# filament_width_sensor_v3_12_opt.net
KiCad netlist of a schematic drawn in EAGLE
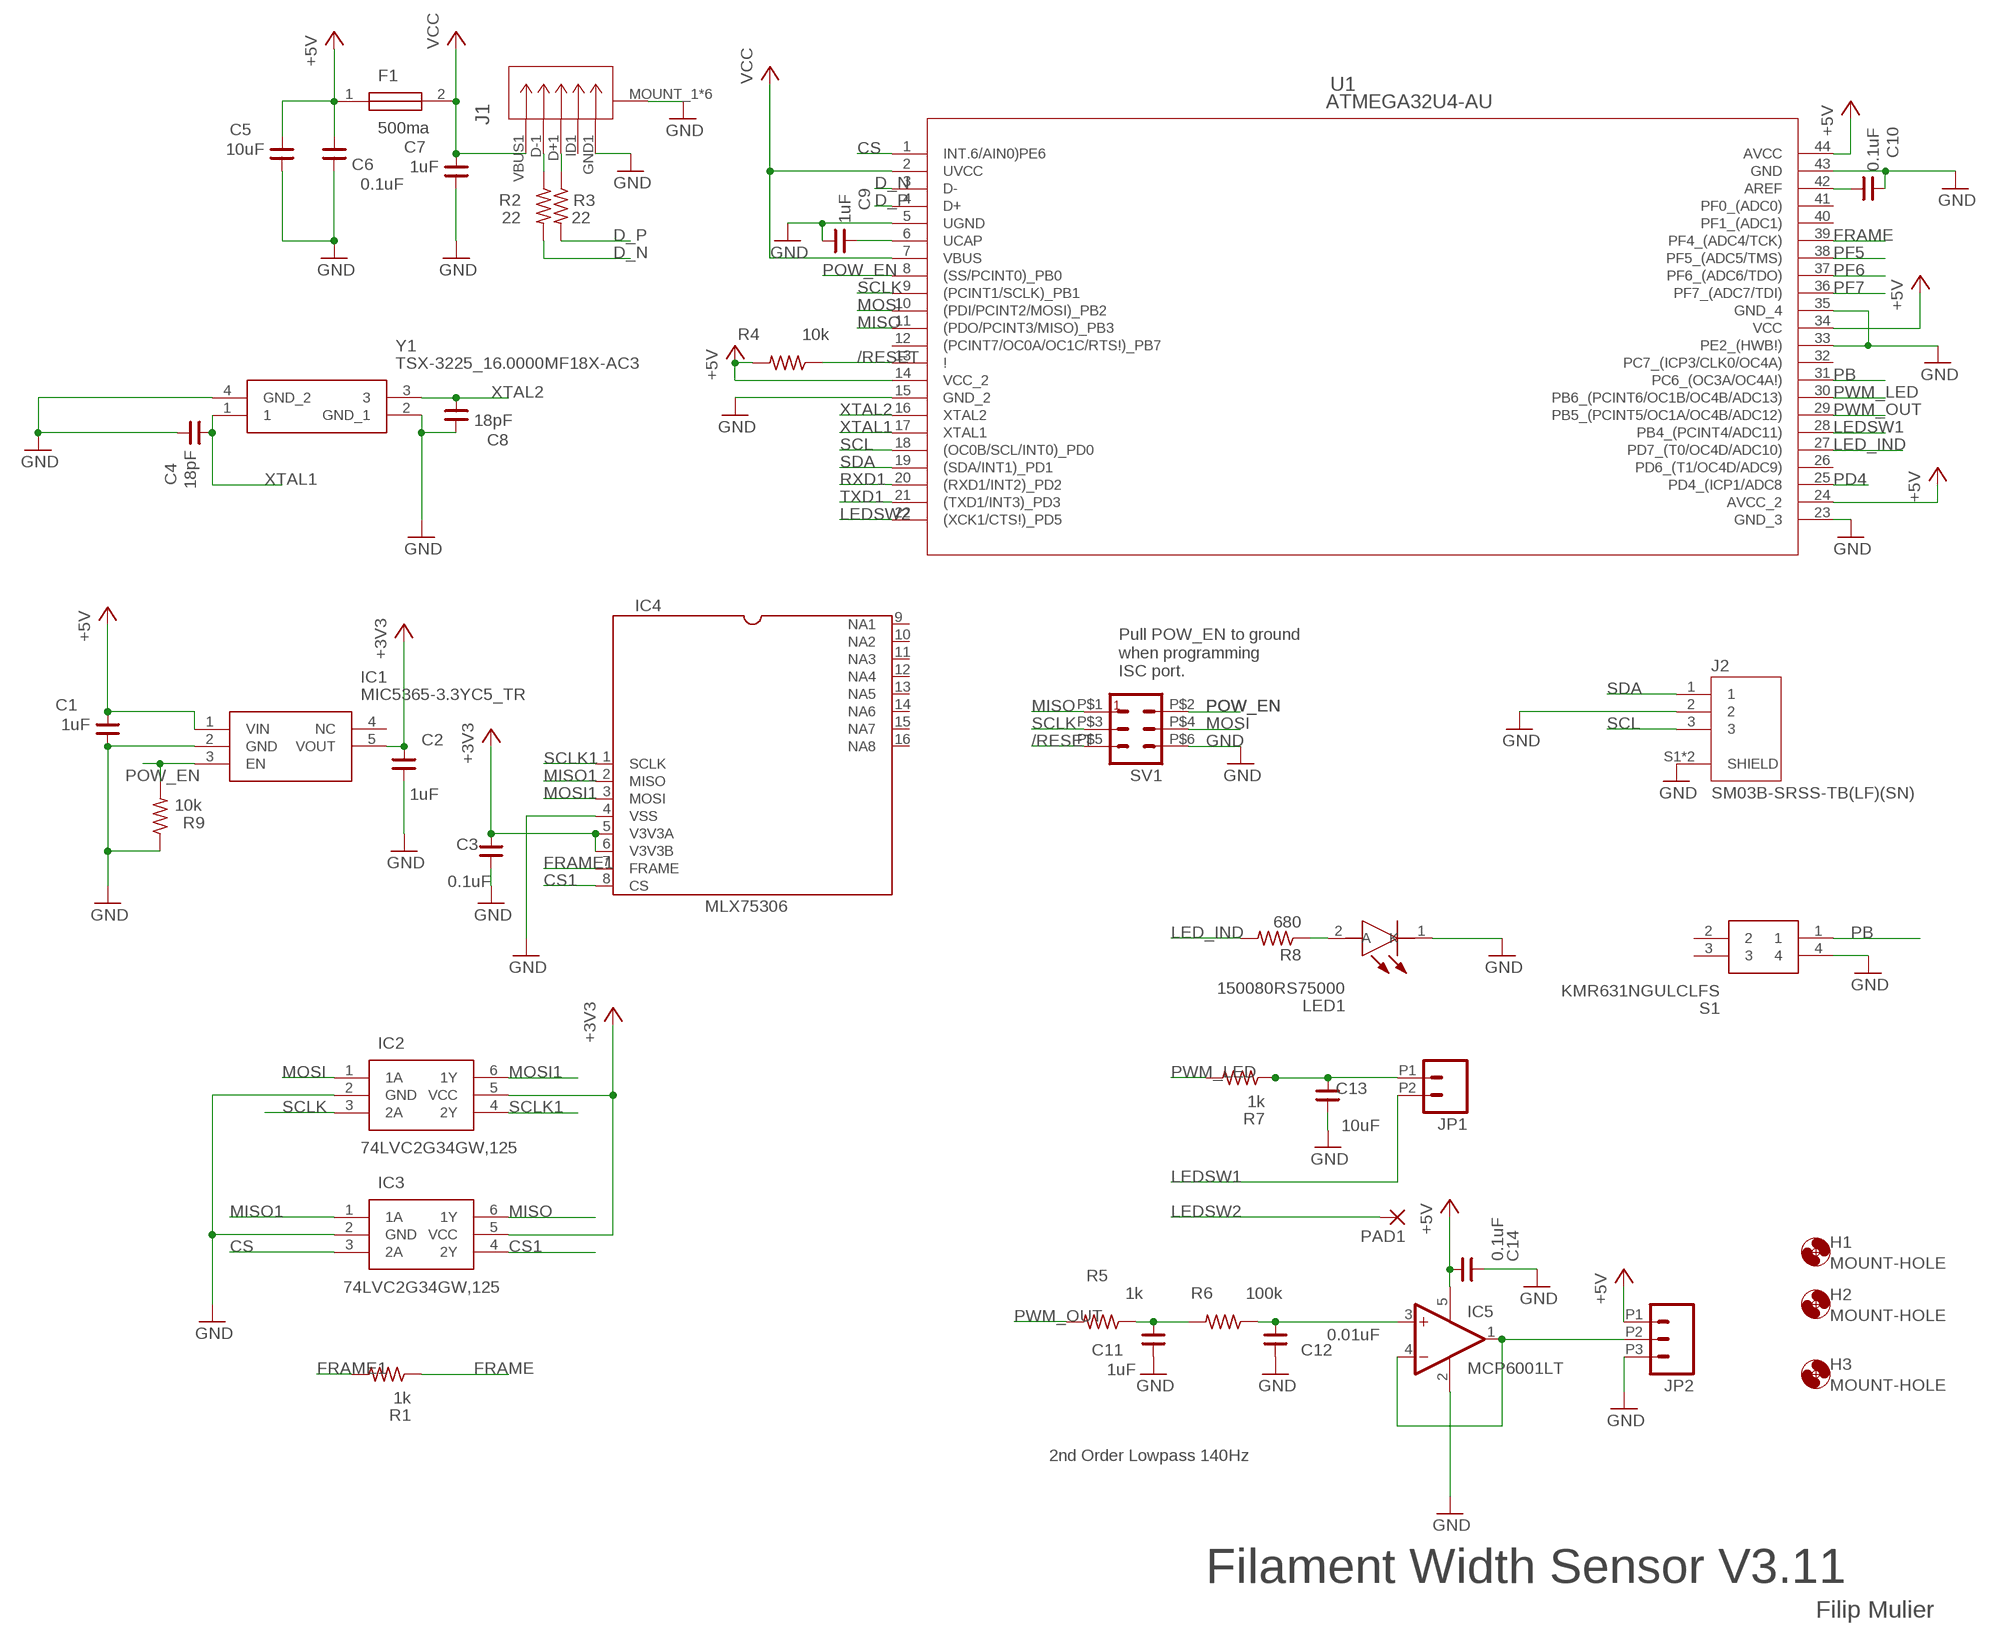
[diagram p0: schematic, sheet 1]

(export (version "E")
  (design (tool "Eeschema 10.0.6"))
  (components
    (comp (ref "C1")
      (value "1uF")
      (footprint "eagle-import:0603")
      (libsource (lib "eagle-import") (part "CNP-0603"))
    )
    (comp (ref "C2")
      (value "1uF")
      (footprint "eagle-import:0603")
      (libsource (lib "eagle-import") (part "CNP-0603"))
    )
    (comp (ref "C3")
      (value "0.1uF")
      (footprint "eagle-import:0603")
      (libsource (lib "eagle-import") (part "CNP-0603"))
    )
    (comp (ref "C4")
      (value "18pF")
      (footprint "eagle-import:0603")
      (libsource (lib "eagle-import") (part "CNP-0603"))
    )
    (comp (ref "C5")
      (value "10uF")
      (footprint "eagle-import:0805")
      (libsource (lib "eagle-import") (part "CNP-0805"))
    )
    (comp (ref "C6")
      (value "0.1uF")
      (footprint "eagle-import:0603")
      (libsource (lib "eagle-import") (part "CNP-0603"))
    )
    (comp (ref "C7")
      (value "1uF")
      (footprint "eagle-import:0603")
      (libsource (lib "eagle-import") (part "CNP-0603"))
    )
    (comp (ref "C8")
      (value "18pF")
      (footprint "eagle-import:0603")
      (libsource (lib "eagle-import") (part "CNP-0603"))
    )
    (comp (ref "C9")
      (value "1uF")
      (footprint "eagle-import:0603")
      (libsource (lib "eagle-import") (part "CNP-0603"))
    )
    (comp (ref "C10")
      (value "0.1uF")
      (footprint "eagle-import:0603")
      (libsource (lib "eagle-import") (part "CNP-0603"))
    )
    (comp (ref "C11")
      (value "1uF")
      (footprint "eagle-import:0603")
      (libsource (lib "eagle-import") (part "CNP-0603"))
    )
    (comp (ref "C12")
      (value "0.01uF")
      (footprint "eagle-import:0603")
      (libsource (lib "eagle-import") (part "CNP-0603"))
    )
    (comp (ref "C13")
      (value "10uF")
      (footprint "eagle-import:0805")
      (libsource (lib "eagle-import") (part "CNP-0805"))
    )
    (comp (ref "C14")
      (value "0.1uF")
      (footprint "eagle-import:0603")
      (libsource (lib "eagle-import") (part "CNP-0603"))
    )
    (comp (ref "F1")
      (value "500ma")
      (footprint "eagle-import:FUSC3216X75N")
      (fields (field (name "MANUFACTURER_PART_NUMBER") "0ZCJ0025FF2E"))
      (libsource (lib "eagle-import") (part "0ZCJ0025FF2E"))
    )
    (comp (ref "H1")
      (value "MOUNT-HOLE")
      (footprint "eagle-import:SCREWHOLE2-56")
      (libsource (lib "eagle-import") (part "MOUNT-HOLE"))
    )
    (comp (ref "H2")
      (value "MOUNT-HOLE")
      (footprint "eagle-import:SCREWHOLE2-56")
      (libsource (lib "eagle-import") (part "MOUNT-HOLE"))
    )
    (comp (ref "H3")
      (value "MOUNT-HOLE")
      (footprint "eagle-import:SCREWHOLE2-56")
      (libsource (lib "eagle-import") (part "MOUNT-HOLE"))
    )
    (comp (ref "IC1")
      (value "MIC5365-3.3YC5_TR")
      (footprint "eagle-import:SOT65P210X110-5N")
      (fields (field (name "MANUFACTURER_PART_NUMBER") "MIC5365-3.0YC5 TR"))
      (libsource (lib "eagle-import") (part "MIC5365-3.0YC5_TR"))
    )
    (comp (ref "IC2")
      (value "74LVC2G34GW,125")
      (footprint "eagle-import:SOP65P210X110-6N")
      (fields (field (name "MOUSER_PART_NUMBER") "771-LVC2G34GW125"))
      (libsource (lib "eagle-import") (part "74LVC2G34GW,125"))
    )
    (comp (ref "IC3")
      (value "74LVC2G34GW,125")
      (footprint "eagle-import:SOP65P210X110-6N")
      (fields (field (name "MOUSER_PART_NUMBER") "771-LVC2G34GW125"))
      (libsource (lib "eagle-import") (part "74LVC2G34GW,125"))
    )
    (comp (ref "IC4")
      (value "MLX75306")
      (footprint "eagle-import:SO16NBC")
      (libsource (lib "eagle-import") (part "MLX75306"))
    )
    (comp (ref "IC5")
      (value "MCP6001LT")
      (footprint "eagle-import:MCP6001_SC70-5")
      (libsource (lib "eagle-import") (part "MCP6001LT"))
    )
    (comp (ref "J1")
      (value "USB")
      (footprint "eagle-import:CONN5_ZX62D-B-5PA8_HIR")
      (fields (field (name "MANUFACTURER_PART_NUMBER") "ZX62D-B-5PA8(30)"))
      (libsource (lib "eagle-import") (part "ZX62D-B-5PA8(30)"))
    )
    (comp (ref "J2")
      (value "SM03B-SRSS-TB(LF)(SN)")
      (footprint "eagle-import:JST_SM03B-SRSS-TB(LF)(SN)")
      (fields (field (name "DIGI-KEY_PART_NUMBER") "455-1803-1-ND") (field (name "MF") "JST Sales"))
      (libsource (lib "eagle-import") (part "SM03B-SRSS-TB(LF)(SN)"))
    )
    (comp (ref "JP1")
      (value "M022.54MM_SCREWTERM")
      (footprint "eagle-import:1X02_2.54_SCREWTERM")
      (libsource (lib "eagle-import") (part "M022.54MM_SCREWTERM"))
    )
    (comp (ref "JP2")
      (value "M03SCREW2.54")
      (footprint "eagle-import:1X03_2.54_SCREWTERM")
      (libsource (lib "eagle-import") (part "M03SCREW2.54"))
    )
    (comp (ref "LED1")
      (value "150080RS75000")
      (footprint "eagle-import:LEDC2012X80N")
      (fields (field (name "MOUSER_PART_NUMBER") "710-150080RS75000"))
      (libsource (lib "eagle-import") (part "150080RS75000"))
    )
    (comp (ref "PAD1")
      (value "WIREPAD1,6/0,8")
      (footprint "eagle-import:1,6_0,8")
      (libsource (lib "eagle-import") (part "WIREPAD1,6/0,8"))
    )
    (comp (ref "R1")
      (value "1k")
      (footprint "eagle-import:R0603")
      (libsource (lib "eagle-import") (part "R-US_R0603"))
    )
    (comp (ref "R2")
      (value "22")
      (footprint "eagle-import:R0603")
      (libsource (lib "eagle-import") (part "R-US_R0603"))
    )
    (comp (ref "R3")
      (value "22")
      (footprint "eagle-import:R0603")
      (libsource (lib "eagle-import") (part "R-US_R0603"))
    )
    (comp (ref "R4")
      (value "10k")
      (footprint "eagle-import:R0603")
      (libsource (lib "eagle-import") (part "R-US_R0603"))
    )
    (comp (ref "R5")
      (value "1k")
      (footprint "eagle-import:R0603")
      (libsource (lib "eagle-import") (part "R-US_R0603"))
    )
    (comp (ref "R6")
      (value "100k")
      (footprint "eagle-import:R0603")
      (libsource (lib "eagle-import") (part "R-US_R0603"))
    )
    (comp (ref "R7")
      (value "1k")
      (footprint "eagle-import:R0603")
      (libsource (lib "eagle-import") (part "R-US_R0603"))
    )
    (comp (ref "R8")
      (value "680")
      (footprint "eagle-import:R0603")
      (libsource (lib "eagle-import") (part "R-US_R0603"))
    )
    (comp (ref "R9")
      (value "10k")
      (footprint "eagle-import:R0603")
      (libsource (lib "eagle-import") (part "R-US_R0603"))
    )
    (comp (ref "S1")
      (value "KMR631NGULCLFS")
      (footprint "eagle-import:KMR621NG")
      (fields (field (name "MOUSER_PART_NUMBER") "611-KMR631NGULCLFS"))
      (libsource (lib "eagle-import") (part "KMR631NGULCLFS"))
    )
    (comp (ref "SV1")
      (value "MA03-2SMD")
      (footprint "eagle-import:MA03-2SMT")
      (libsource (lib "eagle-import") (part "MA03-2SMD"))
    )
    (comp (ref "U1")
      (value "ATMEGA32U4-AU")
      (footprint "eagle-import:44ML_ATM")
      (libsource (lib "eagle-import") (part "ATMEGA32U4-AU"))
    )
    (comp (ref "Y1")
      (value "TSX-3225_16.0000MF18X-AC3")
      (footprint "eagle-import:TSX-3225V")
      (fields
        (field (name "MANUFACTURER_PART_NUMBER") "TSX-3225 16.0000MF18X-AC3")
        (field (name "MOUSER_PART_NUMBER") "732-TX325-16F18X-AC3")
      )
      (libsource (lib "eagle-import") (part "TSX-3225_16.0000MF18X-AC3"))
    )
  )
  (nets
    (net (code "1") (name "+3V3") (class "Default")
      (node (ref "C2") (pin "2") (pinfunction "2_2") (pintype "passive"))
      (node (ref "C3") (pin "2") (pinfunction "2_2") (pintype "passive"))
      (node (ref "IC1") (pin "5") (pinfunction "VOUT_5") (pintype "bidirectional"))
      (node (ref "IC2") (pin "5") (pinfunction "VCC_5") (pintype "bidirectional"))
      (node (ref "IC3") (pin "5") (pinfunction "VCC_5") (pintype "bidirectional"))
      (node (ref "IC4") (pin "5") (pinfunction "V3V3A_5") (pintype "power_in"))
      (node (ref "IC4") (pin "6") (pinfunction "V3V3B_6") (pintype "power_in"))
    )
    (net (code "2") (name "+5V") (class "Default")
      (node (ref "C1") (pin "2") (pinfunction "2_2") (pintype "passive"))
      (node (ref "C14") (pin "2") (pinfunction "2_2") (pintype "passive"))
      (node (ref "C5") (pin "2") (pinfunction "2_2") (pintype "passive"))
      (node (ref "C6") (pin "2") (pinfunction "2_2") (pintype "passive"))
      (node (ref "F1") (pin "1") (pinfunction "1_1") (pintype "bidirectional"))
      (node (ref "IC1") (pin "1") (pinfunction "VIN_1") (pintype "bidirectional"))
      (node (ref "IC5") (pin "5") (pinfunction "V+_5") (pintype "power_in"))
      (node (ref "JP2") (pin "P1") (pinfunction "1_P1") (pintype "passive"))
      (node (ref "R4") (pin "2") (pinfunction "2_2") (pintype "passive"))
      (node (ref "U1") (pin "14") (pinfunction "VCC_2_14") (pintype "power_in"))
      (node (ref "U1") (pin "24") (pinfunction "AVCC_2_24") (pintype "power_in"))
      (node (ref "U1") (pin "34") (pinfunction "VCC_34") (pintype "power_in"))
      (node (ref "U1") (pin "44") (pinfunction "AVCC_44") (pintype "power_in"))
    )
    (net (code "3") (name "/CS") (class "Default")
      (node (ref "IC3") (pin "3") (pinfunction "2A_3") (pintype "bidirectional"))
      (node (ref "U1") (pin "1") (pinfunction "INT.6/AIN0)PE6_1") (pintype "bidirectional"))
    )
    (net (code "4") (name "/CS1") (class "Default")
      (node (ref "IC3") (pin "4") (pinfunction "2Y_4") (pintype "bidirectional"))
      (node (ref "IC4") (pin "8") (pinfunction "CS_8") (pintype "bidirectional"))
    )
    (net (code "5") (name "/D_N") (class "Default")
      (node (ref "R2") (pin "2") (pinfunction "2_2") (pintype "passive"))
      (node (ref "U1") (pin "3") (pinfunction "D-_3") (pintype "passive"))
    )
    (net (code "6") (name "/D_P") (class "Default")
      (node (ref "R3") (pin "2") (pinfunction "2_2") (pintype "passive"))
      (node (ref "U1") (pin "4") (pinfunction "D+_4") (pintype "passive"))
    )
    (net (code "7") (name "/FRAME") (class "Default")
      (node (ref "R1") (pin "1") (pinfunction "1_1") (pintype "passive"))
      (node (ref "U1") (pin "39") (pinfunction "PF4_(ADC4/TCK)_39") (pintype "bidirectional"))
    )
    (net (code "8") (name "/FRAME1") (class "Default")
      (node (ref "IC4") (pin "7") (pinfunction "FRAME_7") (pintype "bidirectional"))
      (node (ref "R1") (pin "2") (pinfunction "2_2") (pintype "passive"))
    )
    (net (code "9") (name "/LEDSW1") (class "Default")
      (node (ref "JP1") (pin "P2") (pinfunction "2_P2") (pintype "passive"))
      (node (ref "U1") (pin "28") (pinfunction "PB4_(PCINT4/ADC11)_28") (pintype "bidirectional"))
    )
    (net (code "10") (name "/LEDSW2") (class "Default")
      (node (ref "PAD1") (pin "1") (pinfunction "P_1") (pintype "passive"))
      (node (ref "U1") (pin "22") (pinfunction "(XCK1/CTS~{})_PD5_22") (pintype "bidirectional"))
    )
    (net (code "11") (name "/LED_IND") (class "Default")
      (node (ref "R8") (pin "2") (pinfunction "2_2") (pintype "passive"))
      (node (ref "U1") (pin "27") (pinfunction "PD7_(T0/OC4D/ADC10)_27") (pintype "bidirectional"))
    )
    (net (code "12") (name "/MISO") (class "Default")
      (node (ref "IC3") (pin "6") (pinfunction "1Y_6") (pintype "bidirectional"))
      (node (ref "SV1") (pin "P$1") (pinfunction "1_P$1") (pintype "passive"))
      (node (ref "U1") (pin "11") (pinfunction "(PDO/PCINT3/MISO)_PB3_11") (pintype "bidirectional"))
    )
    (net (code "13") (name "/MISO1") (class "Default")
      (node (ref "IC3") (pin "1") (pinfunction "1A_1") (pintype "bidirectional"))
      (node (ref "IC4") (pin "2") (pinfunction "MISO_2") (pintype "bidirectional"))
    )
    (net (code "14") (name "/MOSI") (class "Default")
      (node (ref "IC2") (pin "1") (pinfunction "1A_1") (pintype "bidirectional"))
      (node (ref "SV1") (pin "P$4") (pinfunction "4_P$4") (pintype "passive"))
      (node (ref "U1") (pin "10") (pinfunction "(PDI/PCINT2/MOSI)_PB2_10") (pintype "bidirectional"))
    )
    (net (code "15") (name "/MOSI1") (class "Default")
      (node (ref "IC2") (pin "6") (pinfunction "1Y_6") (pintype "bidirectional"))
      (node (ref "IC4") (pin "3") (pinfunction "MOSI_3") (pintype "bidirectional"))
    )
    (net (code "16") (name "/PB") (class "Default")
      (node (ref "S1") (pin "1") (pinfunction "1_1") (pintype "bidirectional"))
      (node (ref "U1") (pin "31") (pinfunction "PC6_(OC3A/OC4A~{})_31") (pintype "bidirectional"))
    )
    (net (code "17") (name "/PD4") (class "Default")
      (node (ref "U1") (pin "25") (pinfunction "PD4_(ICP1/ADC8_25") (pintype "bidirectional"))
    )
    (net (code "18") (name "/PF5") (class "Default")
      (node (ref "U1") (pin "38") (pinfunction "PF5_(ADC5/TMS)_38") (pintype "bidirectional"))
    )
    (net (code "19") (name "/PF6") (class "Default")
      (node (ref "U1") (pin "37") (pinfunction "PF6_(ADC6/TDO)_37") (pintype "bidirectional"))
    )
    (net (code "20") (name "/PF7") (class "Default")
      (node (ref "U1") (pin "36") (pinfunction "PF7_(ADC7/TDI)_36") (pintype "bidirectional"))
    )
    (net (code "21") (name "/POW_EN") (class "Default")
      (node (ref "IC1") (pin "3") (pinfunction "EN_3") (pintype "bidirectional"))
      (node (ref "R9") (pin "2") (pinfunction "2_2") (pintype "passive"))
      (node (ref "SV1") (pin "P$2") (pinfunction "2_P$2") (pintype "passive"))
      (node (ref "U1") (pin "8") (pinfunction "(SS/PCINT0)_PB0_8") (pintype "bidirectional"))
    )
    (net (code "22") (name "/PWM_LED") (class "Default")
      (node (ref "R7") (pin "2") (pinfunction "2_2") (pintype "passive"))
      (node (ref "U1") (pin "30") (pinfunction "PB6_(PCINT6/OC1B/OC4B/ADC13)_30") (pintype "bidirectional"))
    )
    (net (code "23") (name "/PWM_OUT") (class "Default")
      (node (ref "R5") (pin "2") (pinfunction "2_2") (pintype "passive"))
      (node (ref "U1") (pin "29") (pinfunction "PB5_(PCINT5/OC1A/OC4B/ADC12)_29") (pintype "bidirectional"))
    )
    (net (code "24") (name "/RXD1") (class "Default")
      (node (ref "U1") (pin "20") (pinfunction "(RXD1/INT2)_PD2_20") (pintype "bidirectional"))
    )
    (net (code "25") (name "/SCL") (class "Default")
      (node (ref "J2") (pin "3") (pinfunction "3_3") (pintype "passive"))
      (node (ref "U1") (pin "18") (pinfunction "(OC0B/SCL/INT0)_PD0_18") (pintype "bidirectional"))
    )
    (net (code "26") (name "/SCLK") (class "Default")
      (node (ref "IC2") (pin "3") (pinfunction "2A_3") (pintype "bidirectional"))
      (node (ref "SV1") (pin "P$3") (pinfunction "3_P$3") (pintype "passive"))
      (node (ref "U1") (pin "9") (pinfunction "(PCINT1/SCLK)_PB1_9") (pintype "bidirectional"))
    )
    (net (code "27") (name "/SCLK1") (class "Default")
      (node (ref "IC2") (pin "4") (pinfunction "2Y_4") (pintype "bidirectional"))
      (node (ref "IC4") (pin "1") (pinfunction "SCLK_1") (pintype "bidirectional"))
    )
    (net (code "28") (name "/SDA") (class "Default")
      (node (ref "J2") (pin "1") (pinfunction "1_1") (pintype "passive"))
      (node (ref "U1") (pin "19") (pinfunction "(SDA/INT1)_PD1_19") (pintype "bidirectional"))
    )
    (net (code "29") (name "/TXD1") (class "Default")
      (node (ref "U1") (pin "21") (pinfunction "(TXD1/INT3)_PD3_21") (pintype "bidirectional"))
    )
    (net (code "30") (name "/XTAL1") (class "Default")
      (node (ref "C4") (pin "1") (pinfunction "1_1") (pintype "passive"))
      (node (ref "U1") (pin "17") (pinfunction "XTAL1_17") (pintype "input"))
      (node (ref "Y1") (pin "1") (pinfunction "1_1") (pintype "bidirectional"))
    )
    (net (code "31") (name "/XTAL2") (class "Default")
      (node (ref "C8") (pin "1") (pinfunction "1_1") (pintype "passive"))
      (node (ref "U1") (pin "16") (pinfunction "XTAL2_16") (pintype "output"))
      (node (ref "Y1") (pin "3") (pinfunction "3_3") (pintype "bidirectional"))
    )
    (net (code "32") (name "/{slash}RESET") (class "Default")
      (node (ref "R4") (pin "1") (pinfunction "1_1") (pintype "passive"))
      (node (ref "SV1") (pin "P$5") (pinfunction "5_P$5") (pintype "passive"))
      (node (ref "U1") (pin "13") (pinfunction "~_13") (pintype "input"))
    )
    (net (code "33") (name "GND") (class "Default")
      (node (ref "C1") (pin "1") (pinfunction "1_1") (pintype "passive"))
      (node (ref "C10") (pin "2") (pinfunction "2_2") (pintype "passive"))
      (node (ref "C11") (pin "1") (pinfunction "1_1") (pintype "passive"))
      (node (ref "C12") (pin "1") (pinfunction "1_1") (pintype "passive"))
      (node (ref "C13") (pin "1") (pinfunction "1_1") (pintype "passive"))
      (node (ref "C14") (pin "1") (pinfunction "1_1") (pintype "passive"))
      (node (ref "C2") (pin "1") (pinfunction "1_1") (pintype "passive"))
      (node (ref "C3") (pin "1") (pinfunction "1_1") (pintype "passive"))
      (node (ref "C4") (pin "2") (pinfunction "2_2") (pintype "passive"))
      (node (ref "C5") (pin "1") (pinfunction "1_1") (pintype "passive"))
      (node (ref "C6") (pin "1") (pinfunction "1_1") (pintype "passive"))
      (node (ref "C7") (pin "1") (pinfunction "1_1") (pintype "passive"))
      (node (ref "C8") (pin "2") (pinfunction "2_2") (pintype "passive"))
      (node (ref "C9") (pin "1") (pinfunction "1_1") (pintype "passive"))
      (node (ref "IC1") (pin "2") (pinfunction "GND_2") (pintype "bidirectional"))
      (node (ref "IC2") (pin "2") (pinfunction "GND_2") (pintype "bidirectional"))
      (node (ref "IC3") (pin "2") (pinfunction "GND_2") (pintype "bidirectional"))
      (node (ref "IC4") (pin "4") (pinfunction "VSS_4") (pintype "power_in"))
      (node (ref "IC5") (pin "2") (pinfunction "V-_2") (pintype "power_in"))
      (node (ref "J1") (pin "GND1") (pinfunction "GND1_GND1") (pintype "passive"))
      (node (ref "J1") (pin "MOUNT_1") (pinfunction "CASE_GND_MOUNT_1") (pintype "passive"))
      (node (ref "J1") (pin "MOUNT_2") (pinfunction "CASE_GND_MOUNT_2") (pintype "passive"))
      (node (ref "J1") (pin "MOUNT_3") (pinfunction "CASE_GND_MOUNT_3") (pintype "passive"))
      (node (ref "J1") (pin "MOUNT_4") (pinfunction "CASE_GND_MOUNT_4") (pintype "passive"))
      (node (ref "J1") (pin "PAD_1") (pinfunction "CASE_GND_PAD_1") (pintype "passive"))
      (node (ref "J1") (pin "PAD_2") (pinfunction "CASE_GND_PAD_2") (pintype "passive"))
      (node (ref "J2") (pin "2") (pinfunction "2_2") (pintype "passive"))
      (node (ref "J2") (pin "S1") (pinfunction "SHIELD_S1") (pintype "passive"))
      (node (ref "J2") (pin "S2") (pinfunction "SHIELD_S2") (pintype "passive"))
      (node (ref "JP2") (pin "P3") (pinfunction "3_P3") (pintype "passive"))
      (node (ref "LED1") (pin "1") (pinfunction "K_1") (pintype "bidirectional"))
      (node (ref "R9") (pin "1") (pinfunction "1_1") (pintype "passive"))
      (node (ref "S1") (pin "4") (pinfunction "4_4") (pintype "bidirectional"))
      (node (ref "SV1") (pin "P$6") (pinfunction "6_P$6") (pintype "passive"))
      (node (ref "U1") (pin "15") (pinfunction "GND_2_15") (pintype "power_in"))
      (node (ref "U1") (pin "23") (pinfunction "GND_3_23") (pintype "power_in"))
      (node (ref "U1") (pin "33") (pinfunction "PE2_(HWB~{})_33") (pintype "bidirectional"))
      (node (ref "U1") (pin "35") (pinfunction "GND_4_35") (pintype "power_in"))
      (node (ref "U1") (pin "43") (pinfunction "GND_43") (pintype "power_in"))
      (node (ref "U1") (pin "5") (pinfunction "UGND_5") (pintype "power_in"))
      (node (ref "Y1") (pin "2") (pinfunction "GND_1_2") (pintype "bidirectional"))
      (node (ref "Y1") (pin "4") (pinfunction "GND_2_4") (pintype "bidirectional"))
    )
    (net (code "34") (name "Net-(C11-Pad2)") (class "Default")
      (node (ref "C11") (pin "2") (pinfunction "2_2") (pintype "passive"))
      (node (ref "R5") (pin "1") (pinfunction "1_1") (pintype "passive"))
      (node (ref "R6") (pin "2") (pinfunction "2_2") (pintype "passive"))
    )
    (net (code "35") (name "Net-(IC5-+IN)") (class "Default")
      (node (ref "C12") (pin "2") (pinfunction "2_2") (pintype "passive"))
      (node (ref "IC5") (pin "3") (pinfunction "+IN_3") (pintype "input"))
      (node (ref "R6") (pin "1") (pinfunction "1_1") (pintype "passive"))
    )
    (net (code "36") (name "Net-(IC5--IN)") (class "Default")
      (node (ref "IC5") (pin "1") (pinfunction "OUT_1") (pintype "output"))
      (node (ref "IC5") (pin "4") (pinfunction "-IN_4") (pintype "input"))
      (node (ref "JP2") (pin "P2") (pinfunction "2_P2") (pintype "passive"))
    )
    (net (code "37") (name "Net-(J1-PadD+1)") (class "Default")
      (node (ref "J1") (pin "D+1") (pinfunction "D+1_D+1") (pintype "passive"))
      (node (ref "R3") (pin "1") (pinfunction "1_1") (pintype "passive"))
    )
    (net (code "38") (name "Net-(J1-PadD-1)") (class "Default")
      (node (ref "J1") (pin "D-1") (pinfunction "D-1_D-1") (pintype "passive"))
      (node (ref "R2") (pin "1") (pinfunction "1_1") (pintype "passive"))
    )
    (net (code "39") (name "Net-(JP1-1)") (class "Default")
      (node (ref "C13") (pin "2") (pinfunction "2_2") (pintype "passive"))
      (node (ref "JP1") (pin "P1") (pinfunction "1_P1") (pintype "passive"))
      (node (ref "R7") (pin "1") (pinfunction "1_1") (pintype "passive"))
    )
    (net (code "40") (name "Net-(LED1-A)") (class "Default")
      (node (ref "LED1") (pin "2") (pinfunction "A_2") (pintype "bidirectional"))
      (node (ref "R8") (pin "1") (pinfunction "1_1") (pintype "passive"))
    )
    (net (code "41") (name "Net-(U1-AREF)") (class "Default")
      (node (ref "C10") (pin "1") (pinfunction "1_1") (pintype "passive"))
      (node (ref "U1") (pin "42") (pinfunction "AREF_42") (pintype "passive"))
    )
    (net (code "42") (name "Net-(U1-UCAP)") (class "Default")
      (node (ref "C9") (pin "2") (pinfunction "2_2") (pintype "passive"))
      (node (ref "U1") (pin "6") (pinfunction "UCAP_6") (pintype "power_in"))
    )
    (net (code "43") (name "VCC") (class "Default")
      (node (ref "C7") (pin "2") (pinfunction "2_2") (pintype "passive"))
      (node (ref "F1") (pin "2") (pinfunction "2_2") (pintype "bidirectional"))
      (node (ref "J1") (pin "VBUS1") (pinfunction "VBUS1_VBUS1") (pintype "passive"))
      (node (ref "U1") (pin "2") (pinfunction "UVCC_2") (pintype "power_in"))
      (node (ref "U1") (pin "7") (pinfunction "VBUS_7") (pintype "power_in"))
    )
    (net (code "44") (name "unconnected-(IC1-NC-Pad4)") (class "Default")
      (node (ref "IC1") (pin "4") (pinfunction "NC_4") (pintype "no_connect"))
    )
    (net (code "45") (name "unconnected-(IC4-NA1-Pad9)") (class "Default")
      (node (ref "IC4") (pin "9") (pinfunction "NA1_9") (pintype "bidirectional"))
    )
    (net (code "46") (name "unconnected-(IC4-NA2-Pad10)") (class "Default")
      (node (ref "IC4") (pin "10") (pinfunction "NA2_10") (pintype "bidirectional"))
    )
    (net (code "47") (name "unconnected-(IC4-NA3-Pad11)") (class "Default")
      (node (ref "IC4") (pin "11") (pinfunction "NA3_11") (pintype "bidirectional"))
    )
    (net (code "48") (name "unconnected-(IC4-NA4-Pad12)") (class "Default")
      (node (ref "IC4") (pin "12") (pinfunction "NA4_12") (pintype "bidirectional"))
    )
    (net (code "49") (name "unconnected-(IC4-NA5-Pad13)") (class "Default")
      (node (ref "IC4") (pin "13") (pinfunction "NA5_13") (pintype "bidirectional"))
    )
    (net (code "50") (name "unconnected-(IC4-NA6-Pad14)") (class "Default")
      (node (ref "IC4") (pin "14") (pinfunction "NA6_14") (pintype "bidirectional"))
    )
    (net (code "51") (name "unconnected-(IC4-NA7-Pad15)") (class "Default")
      (node (ref "IC4") (pin "15") (pinfunction "NA7_15") (pintype "bidirectional"))
    )
    (net (code "52") (name "unconnected-(IC4-NA8-Pad16)") (class "Default")
      (node (ref "IC4") (pin "16") (pinfunction "NA8_16") (pintype "bidirectional"))
    )
    (net (code "53") (name "unconnected-(J1-PadID1)") (class "Default")
      (node (ref "J1") (pin "ID1") (pinfunction "ID1_ID1") (pintype "passive"))
    )
    (net (code "54") (name "unconnected-(S1-Pad2)") (class "Default")
      (node (ref "S1") (pin "2") (pinfunction "2_2") (pintype "bidirectional"))
    )
    (net (code "55") (name "unconnected-(S1-Pad3)") (class "Default")
      (node (ref "S1") (pin "3") (pinfunction "3_3") (pintype "bidirectional"))
    )
    (net (code "56") (name "unconnected-(U1-(PCINT7{slash}OC0A{slash}OC1C{slash}RTS~{})_PB7-Pad12)") (class "Default")
      (node (ref "U1") (pin "12") (pinfunction "(PCINT7/OC0A/OC1C/RTS~{})_PB7_12") (pintype "bidirectional"))
    )
    (net (code "57") (name "unconnected-(U1-PC7_(ICP3{slash}CLK0{slash}OC4A)-Pad32)") (class "Default")
      (node (ref "U1") (pin "32") (pinfunction "PC7_(ICP3/CLK0/OC4A)_32") (pintype "bidirectional"))
    )
    (net (code "58") (name "unconnected-(U1-PD6_(T1{slash}OC4D{slash}ADC9)-Pad26)") (class "Default")
      (node (ref "U1") (pin "26") (pinfunction "PD6_(T1/OC4D/ADC9)_26") (pintype "bidirectional"))
    )
    (net (code "59") (name "unconnected-(U1-PF0_(ADC0)-Pad41)") (class "Default")
      (node (ref "U1") (pin "41") (pinfunction "PF0_(ADC0)_41") (pintype "bidirectional"))
    )
    (net (code "60") (name "unconnected-(U1-PF1_(ADC1)-Pad40)") (class "Default")
      (node (ref "U1") (pin "40") (pinfunction "PF1_(ADC1)_40") (pintype "bidirectional"))
    )
  )
)
